# matrix_corin.net
KiCad netlist of a schematic drawn in Altium Designer
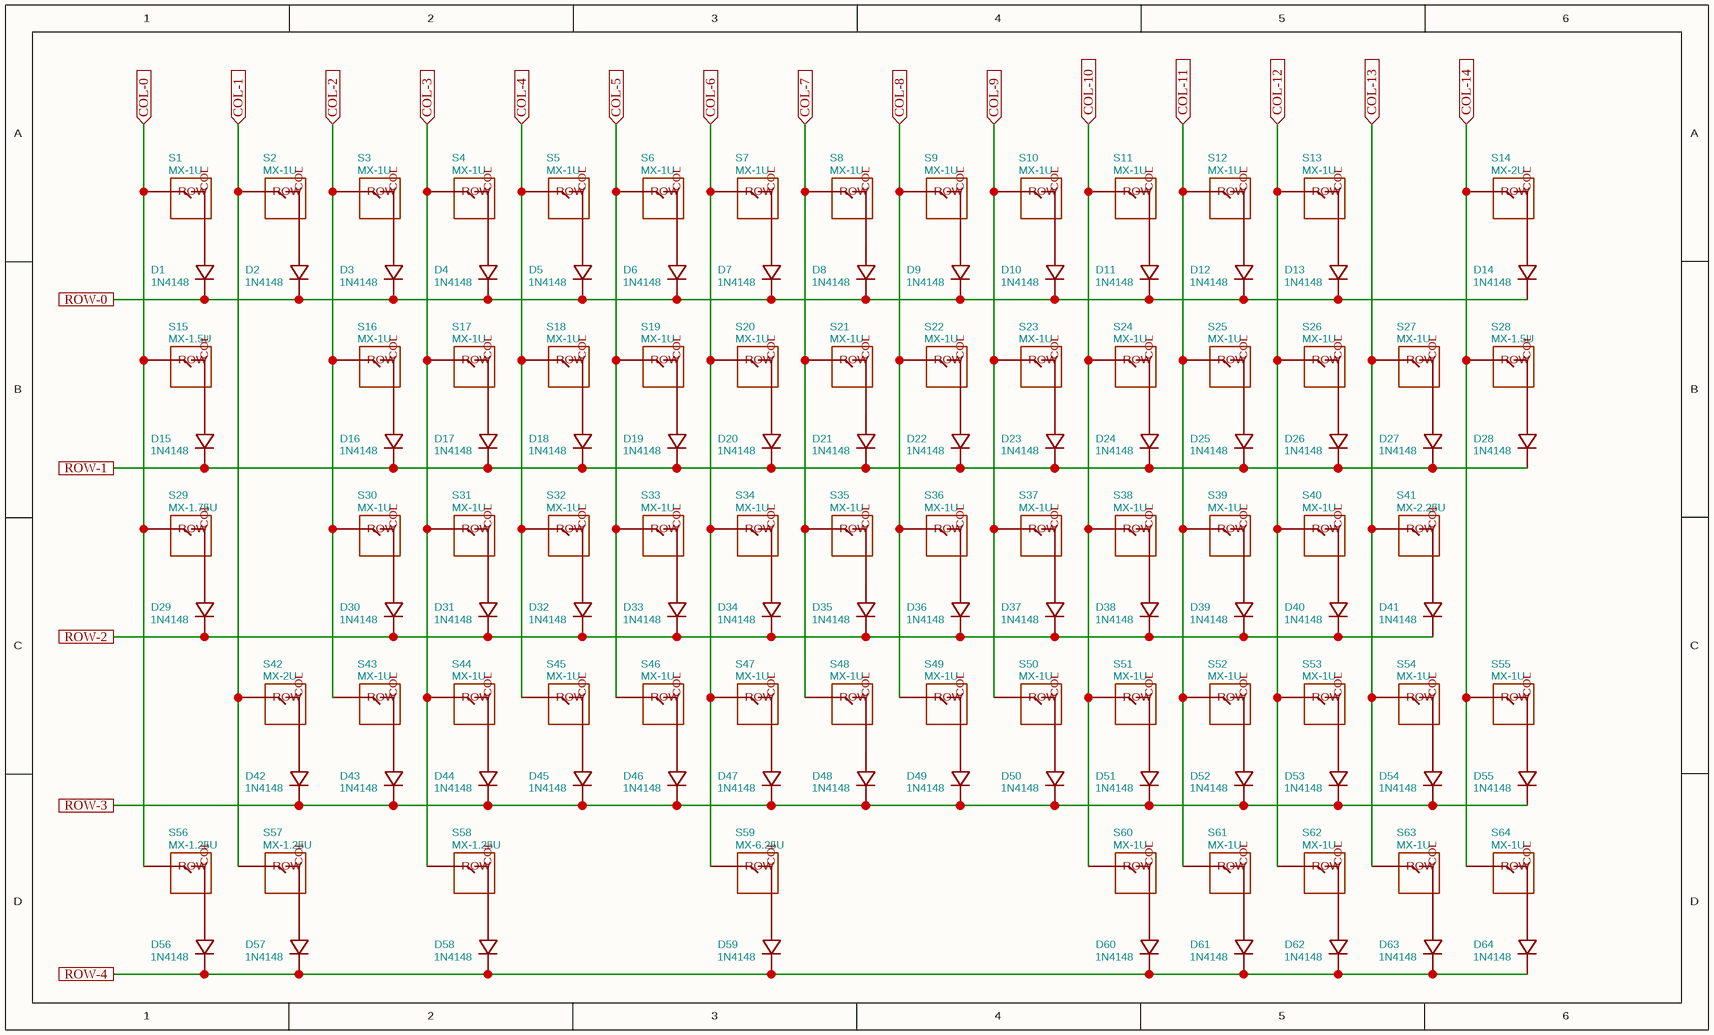
[diagram p0: matrix_corin.schdoc]

(export (version "E")
  (design (tool "Eeschema 10.0.6"))
  (components
    (comp (ref "D1")
      (value "1N4148")
      (fields (field (name "BOM_MANUFACTURER PART") "1N4148W") (field (name "BOM_SUPPLIER PART") "C115103"))
      (libsource (lib "altium-import") (part "root_1_1N4148_"))
    )
    (comp (ref "D2")
      (value "1N4148")
      (fields (field (name "BOM_MANUFACTURER PART") "1N4148W") (field (name "BOM_SUPPLIER PART") "C115103"))
      (libsource (lib "altium-import") (part "root_1_1N4148_"))
    )
    (comp (ref "D3")
      (value "1N4148")
      (fields (field (name "BOM_MANUFACTURER PART") "1N4148W") (field (name "BOM_SUPPLIER PART") "C115103"))
      (libsource (lib "altium-import") (part "root_1_1N4148_"))
    )
    (comp (ref "D4")
      (value "1N4148")
      (fields (field (name "BOM_MANUFACTURER PART") "1N4148W") (field (name "BOM_SUPPLIER PART") "C115103"))
      (libsource (lib "altium-import") (part "root_1_1N4148_"))
    )
    (comp (ref "D5")
      (value "1N4148")
      (fields (field (name "BOM_MANUFACTURER PART") "1N4148W") (field (name "BOM_SUPPLIER PART") "C115103"))
      (libsource (lib "altium-import") (part "root_1_1N4148_"))
    )
    (comp (ref "D6")
      (value "1N4148")
      (fields (field (name "BOM_MANUFACTURER PART") "1N4148W") (field (name "BOM_SUPPLIER PART") "C115103"))
      (libsource (lib "altium-import") (part "root_1_1N4148_"))
    )
    (comp (ref "D7")
      (value "1N4148")
      (fields (field (name "BOM_MANUFACTURER PART") "1N4148W") (field (name "BOM_SUPPLIER PART") "C115103"))
      (libsource (lib "altium-import") (part "root_1_1N4148_"))
    )
    (comp (ref "D8")
      (value "1N4148")
      (fields (field (name "BOM_MANUFACTURER PART") "1N4148W") (field (name "BOM_SUPPLIER PART") "C115103"))
      (libsource (lib "altium-import") (part "root_1_1N4148_"))
    )
    (comp (ref "D9")
      (value "1N4148")
      (fields (field (name "BOM_MANUFACTURER PART") "1N4148W") (field (name "BOM_SUPPLIER PART") "C115103"))
      (libsource (lib "altium-import") (part "root_1_1N4148_"))
    )
    (comp (ref "D10")
      (value "1N4148")
      (fields (field (name "BOM_MANUFACTURER PART") "1N4148W") (field (name "BOM_SUPPLIER PART") "C115103"))
      (libsource (lib "altium-import") (part "root_1_1N4148_"))
    )
    (comp (ref "D11")
      (value "1N4148")
      (fields (field (name "BOM_MANUFACTURER PART") "1N4148W") (field (name "BOM_SUPPLIER PART") "C115103"))
      (libsource (lib "altium-import") (part "root_1_1N4148_"))
    )
    (comp (ref "D12")
      (value "1N4148")
      (fields (field (name "BOM_MANUFACTURER PART") "1N4148W") (field (name "BOM_SUPPLIER PART") "C115103"))
      (libsource (lib "altium-import") (part "root_1_1N4148_"))
    )
    (comp (ref "D13")
      (value "1N4148")
      (fields (field (name "BOM_MANUFACTURER PART") "1N4148W") (field (name "BOM_SUPPLIER PART") "C115103"))
      (libsource (lib "altium-import") (part "root_1_1N4148_"))
    )
    (comp (ref "D14")
      (value "1N4148")
      (fields (field (name "BOM_MANUFACTURER PART") "1N4148W") (field (name "BOM_SUPPLIER PART") "C115103"))
      (libsource (lib "altium-import") (part "root_1_1N4148_"))
    )
    (comp (ref "D15")
      (value "1N4148")
      (fields (field (name "BOM_MANUFACTURER PART") "1N4148W") (field (name "BOM_SUPPLIER PART") "C115103"))
      (libsource (lib "altium-import") (part "root_1_1N4148_"))
    )
    (comp (ref "D16")
      (value "1N4148")
      (fields (field (name "BOM_MANUFACTURER PART") "1N4148W") (field (name "BOM_SUPPLIER PART") "C115103"))
      (libsource (lib "altium-import") (part "root_1_1N4148_"))
    )
    (comp (ref "D17")
      (value "1N4148")
      (fields (field (name "BOM_MANUFACTURER PART") "1N4148W") (field (name "BOM_SUPPLIER PART") "C115103"))
      (libsource (lib "altium-import") (part "root_1_1N4148_"))
    )
    (comp (ref "D18")
      (value "1N4148")
      (fields (field (name "BOM_MANUFACTURER PART") "1N4148W") (field (name "BOM_SUPPLIER PART") "C115103"))
      (libsource (lib "altium-import") (part "root_1_1N4148_"))
    )
    (comp (ref "D19")
      (value "1N4148")
      (fields (field (name "BOM_MANUFACTURER PART") "1N4148W") (field (name "BOM_SUPPLIER PART") "C115103"))
      (libsource (lib "altium-import") (part "root_1_1N4148_"))
    )
    (comp (ref "D20")
      (value "1N4148")
      (fields (field (name "BOM_MANUFACTURER PART") "1N4148W") (field (name "BOM_SUPPLIER PART") "C115103"))
      (libsource (lib "altium-import") (part "root_1_1N4148_"))
    )
    (comp (ref "D21")
      (value "1N4148")
      (fields (field (name "BOM_MANUFACTURER PART") "1N4148W") (field (name "BOM_SUPPLIER PART") "C115103"))
      (libsource (lib "altium-import") (part "root_1_1N4148_"))
    )
    (comp (ref "D22")
      (value "1N4148")
      (fields (field (name "BOM_MANUFACTURER PART") "1N4148W") (field (name "BOM_SUPPLIER PART") "C115103"))
      (libsource (lib "altium-import") (part "root_1_1N4148_"))
    )
    (comp (ref "D23")
      (value "1N4148")
      (fields (field (name "BOM_MANUFACTURER PART") "1N4148W") (field (name "BOM_SUPPLIER PART") "C115103"))
      (libsource (lib "altium-import") (part "root_1_1N4148_"))
    )
    (comp (ref "D24")
      (value "1N4148")
      (fields (field (name "BOM_MANUFACTURER PART") "1N4148W") (field (name "BOM_SUPPLIER PART") "C115103"))
      (libsource (lib "altium-import") (part "root_1_1N4148_"))
    )
    (comp (ref "D25")
      (value "1N4148")
      (fields (field (name "BOM_MANUFACTURER PART") "1N4148W") (field (name "BOM_SUPPLIER PART") "C115103"))
      (libsource (lib "altium-import") (part "root_1_1N4148_"))
    )
    (comp (ref "D26")
      (value "1N4148")
      (fields (field (name "BOM_MANUFACTURER PART") "1N4148W") (field (name "BOM_SUPPLIER PART") "C115103"))
      (libsource (lib "altium-import") (part "root_1_1N4148_"))
    )
    (comp (ref "D27")
      (value "1N4148")
      (fields (field (name "BOM_MANUFACTURER PART") "1N4148W") (field (name "BOM_SUPPLIER PART") "C115103"))
      (libsource (lib "altium-import") (part "root_1_1N4148_"))
    )
    (comp (ref "D28")
      (value "1N4148")
      (fields (field (name "BOM_MANUFACTURER PART") "1N4148W") (field (name "BOM_SUPPLIER PART") "C115103"))
      (libsource (lib "altium-import") (part "root_1_1N4148_"))
    )
    (comp (ref "D29")
      (value "1N4148")
      (fields (field (name "BOM_MANUFACTURER PART") "1N4148W") (field (name "BOM_SUPPLIER PART") "C115103"))
      (libsource (lib "altium-import") (part "root_1_1N4148_"))
    )
    (comp (ref "D30")
      (value "1N4148")
      (fields (field (name "BOM_MANUFACTURER PART") "1N4148W") (field (name "BOM_SUPPLIER PART") "C115103"))
      (libsource (lib "altium-import") (part "root_1_1N4148_"))
    )
    (comp (ref "D31")
      (value "1N4148")
      (fields (field (name "BOM_MANUFACTURER PART") "1N4148W") (field (name "BOM_SUPPLIER PART") "C115103"))
      (libsource (lib "altium-import") (part "root_1_1N4148_"))
    )
    (comp (ref "D32")
      (value "1N4148")
      (fields (field (name "BOM_MANUFACTURER PART") "1N4148W") (field (name "BOM_SUPPLIER PART") "C115103"))
      (libsource (lib "altium-import") (part "root_1_1N4148_"))
    )
    (comp (ref "D33")
      (value "1N4148")
      (fields (field (name "BOM_MANUFACTURER PART") "1N4148W") (field (name "BOM_SUPPLIER PART") "C115103"))
      (libsource (lib "altium-import") (part "root_1_1N4148_"))
    )
    (comp (ref "D34")
      (value "1N4148")
      (fields (field (name "BOM_MANUFACTURER PART") "1N4148W") (field (name "BOM_SUPPLIER PART") "C115103"))
      (libsource (lib "altium-import") (part "root_1_1N4148_"))
    )
    (comp (ref "D35")
      (value "1N4148")
      (fields (field (name "BOM_MANUFACTURER PART") "1N4148W") (field (name "BOM_SUPPLIER PART") "C115103"))
      (libsource (lib "altium-import") (part "root_1_1N4148_"))
    )
    (comp (ref "D36")
      (value "1N4148")
      (fields (field (name "BOM_MANUFACTURER PART") "1N4148W") (field (name "BOM_SUPPLIER PART") "C115103"))
      (libsource (lib "altium-import") (part "root_1_1N4148_"))
    )
    (comp (ref "D37")
      (value "1N4148")
      (fields (field (name "BOM_MANUFACTURER PART") "1N4148W") (field (name "BOM_SUPPLIER PART") "C115103"))
      (libsource (lib "altium-import") (part "root_1_1N4148_"))
    )
    (comp (ref "D38")
      (value "1N4148")
      (fields (field (name "BOM_MANUFACTURER PART") "1N4148W") (field (name "BOM_SUPPLIER PART") "C115103"))
      (libsource (lib "altium-import") (part "root_1_1N4148_"))
    )
    (comp (ref "D39")
      (value "1N4148")
      (fields (field (name "BOM_MANUFACTURER PART") "1N4148W") (field (name "BOM_SUPPLIER PART") "C115103"))
      (libsource (lib "altium-import") (part "root_1_1N4148_"))
    )
    (comp (ref "D40")
      (value "1N4148")
      (fields (field (name "BOM_MANUFACTURER PART") "1N4148W") (field (name "BOM_SUPPLIER PART") "C115103"))
      (libsource (lib "altium-import") (part "root_1_1N4148_"))
    )
    (comp (ref "D41")
      (value "1N4148")
      (fields (field (name "BOM_MANUFACTURER PART") "1N4148W") (field (name "BOM_SUPPLIER PART") "C115103"))
      (libsource (lib "altium-import") (part "root_1_1N4148_"))
    )
    (comp (ref "D42")
      (value "1N4148")
      (fields (field (name "BOM_MANUFACTURER PART") "1N4148W") (field (name "BOM_SUPPLIER PART") "C115103"))
      (libsource (lib "altium-import") (part "root_1_1N4148_"))
    )
    (comp (ref "D43")
      (value "1N4148")
      (fields (field (name "BOM_MANUFACTURER PART") "1N4148W") (field (name "BOM_SUPPLIER PART") "C115103"))
      (libsource (lib "altium-import") (part "root_1_1N4148_"))
    )
    (comp (ref "D44")
      (value "1N4148")
      (fields (field (name "BOM_MANUFACTURER PART") "1N4148W") (field (name "BOM_SUPPLIER PART") "C115103"))
      (libsource (lib "altium-import") (part "root_1_1N4148_"))
    )
    (comp (ref "D45")
      (value "1N4148")
      (fields (field (name "BOM_MANUFACTURER PART") "1N4148W") (field (name "BOM_SUPPLIER PART") "C115103"))
      (libsource (lib "altium-import") (part "root_1_1N4148_"))
    )
    (comp (ref "D46")
      (value "1N4148")
      (fields (field (name "BOM_MANUFACTURER PART") "1N4148W") (field (name "BOM_SUPPLIER PART") "C115103"))
      (libsource (lib "altium-import") (part "root_1_1N4148_"))
    )
    (comp (ref "D47")
      (value "1N4148")
      (fields (field (name "BOM_MANUFACTURER PART") "1N4148W") (field (name "BOM_SUPPLIER PART") "C115103"))
      (libsource (lib "altium-import") (part "root_1_1N4148_"))
    )
    (comp (ref "D48")
      (value "1N4148")
      (fields (field (name "BOM_MANUFACTURER PART") "1N4148W") (field (name "BOM_SUPPLIER PART") "C115103"))
      (libsource (lib "altium-import") (part "root_1_1N4148_"))
    )
    (comp (ref "D49")
      (value "1N4148")
      (fields (field (name "BOM_MANUFACTURER PART") "1N4148W") (field (name "BOM_SUPPLIER PART") "C115103"))
      (libsource (lib "altium-import") (part "root_1_1N4148_"))
    )
    (comp (ref "D50")
      (value "1N4148")
      (fields (field (name "BOM_MANUFACTURER PART") "1N4148W") (field (name "BOM_SUPPLIER PART") "C115103"))
      (libsource (lib "altium-import") (part "root_1_1N4148_"))
    )
    (comp (ref "D51")
      (value "1N4148")
      (fields (field (name "BOM_MANUFACTURER PART") "1N4148W") (field (name "BOM_SUPPLIER PART") "C115103"))
      (libsource (lib "altium-import") (part "root_1_1N4148_"))
    )
    (comp (ref "D52")
      (value "1N4148")
      (fields (field (name "BOM_MANUFACTURER PART") "1N4148W") (field (name "BOM_SUPPLIER PART") "C115103"))
      (libsource (lib "altium-import") (part "root_1_1N4148_"))
    )
    (comp (ref "D53")
      (value "1N4148")
      (fields (field (name "BOM_MANUFACTURER PART") "1N4148W") (field (name "BOM_SUPPLIER PART") "C115103"))
      (libsource (lib "altium-import") (part "root_1_1N4148_"))
    )
    (comp (ref "D54")
      (value "1N4148")
      (fields (field (name "BOM_MANUFACTURER PART") "1N4148W") (field (name "BOM_SUPPLIER PART") "C115103"))
      (libsource (lib "altium-import") (part "root_1_1N4148_"))
    )
    (comp (ref "D55")
      (value "1N4148")
      (fields (field (name "BOM_MANUFACTURER PART") "1N4148W") (field (name "BOM_SUPPLIER PART") "C115103"))
      (libsource (lib "altium-import") (part "root_1_1N4148_"))
    )
    (comp (ref "D56")
      (value "1N4148")
      (fields (field (name "BOM_MANUFACTURER PART") "1N4148W") (field (name "BOM_SUPPLIER PART") "C115103"))
      (libsource (lib "altium-import") (part "root_1_1N4148_"))
    )
    (comp (ref "D57")
      (value "1N4148")
      (fields (field (name "BOM_MANUFACTURER PART") "1N4148W") (field (name "BOM_SUPPLIER PART") "C115103"))
      (libsource (lib "altium-import") (part "root_1_1N4148_"))
    )
    (comp (ref "D58")
      (value "1N4148")
      (fields (field (name "BOM_MANUFACTURER PART") "1N4148W") (field (name "BOM_SUPPLIER PART") "C115103"))
      (libsource (lib "altium-import") (part "root_1_1N4148_"))
    )
    (comp (ref "D59")
      (value "1N4148")
      (fields (field (name "BOM_MANUFACTURER PART") "1N4148W") (field (name "BOM_SUPPLIER PART") "C115103"))
      (libsource (lib "altium-import") (part "root_1_1N4148_"))
    )
    (comp (ref "D60")
      (value "1N4148")
      (fields (field (name "BOM_MANUFACTURER PART") "1N4148W") (field (name "BOM_SUPPLIER PART") "C115103"))
      (libsource (lib "altium-import") (part "root_1_1N4148_"))
    )
    (comp (ref "D61")
      (value "1N4148")
      (fields (field (name "BOM_MANUFACTURER PART") "1N4148W") (field (name "BOM_SUPPLIER PART") "C115103"))
      (libsource (lib "altium-import") (part "root_1_1N4148_"))
    )
    (comp (ref "D62")
      (value "1N4148")
      (fields (field (name "BOM_MANUFACTURER PART") "1N4148W") (field (name "BOM_SUPPLIER PART") "C115103"))
      (libsource (lib "altium-import") (part "root_1_1N4148_"))
    )
    (comp (ref "D63")
      (value "1N4148")
      (fields (field (name "BOM_MANUFACTURER PART") "1N4148W") (field (name "BOM_SUPPLIER PART") "C115103"))
      (libsource (lib "altium-import") (part "root_1_1N4148_"))
    )
    (comp (ref "D64")
      (value "1N4148")
      (fields (field (name "BOM_MANUFACTURER PART") "1N4148W") (field (name "BOM_SUPPLIER PART") "C115103"))
      (libsource (lib "altium-import") (part "root_1_1N4148_"))
    )
    (comp (ref "S1")
      (value "MX-1U")
      (fields (field (name "BOM_MANUFACTURER PART") "Cherry MX") (field (name "CONTRIBUTOR") "Longnald"))
      (libsource (lib "altium-import") (part "root_0_MX-1U_"))
    )
    (comp (ref "S2")
      (value "MX-1U")
      (fields (field (name "BOM_MANUFACTURER PART") "Cherry MX") (field (name "CONTRIBUTOR") "Longnald"))
      (libsource (lib "altium-import") (part "root_0_MX-1U_"))
    )
    (comp (ref "S3")
      (value "MX-1U")
      (fields (field (name "BOM_MANUFACTURER PART") "Cherry MX") (field (name "CONTRIBUTOR") "Longnald"))
      (libsource (lib "altium-import") (part "root_0_MX-1U_"))
    )
    (comp (ref "S4")
      (value "MX-1U")
      (fields (field (name "BOM_MANUFACTURER PART") "Cherry MX") (field (name "CONTRIBUTOR") "Longnald"))
      (libsource (lib "altium-import") (part "root_0_MX-1U_"))
    )
    (comp (ref "S5")
      (value "MX-1U")
      (fields (field (name "BOM_MANUFACTURER PART") "Cherry MX") (field (name "CONTRIBUTOR") "Longnald"))
      (libsource (lib "altium-import") (part "root_0_MX-1U_"))
    )
    (comp (ref "S6")
      (value "MX-1U")
      (fields (field (name "BOM_MANUFACTURER PART") "Cherry MX") (field (name "CONTRIBUTOR") "Longnald"))
      (libsource (lib "altium-import") (part "root_0_MX-1U_"))
    )
    (comp (ref "S7")
      (value "MX-1U")
      (fields (field (name "BOM_MANUFACTURER PART") "Cherry MX") (field (name "CONTRIBUTOR") "Longnald"))
      (libsource (lib "altium-import") (part "root_0_MX-1U_"))
    )
    (comp (ref "S8")
      (value "MX-1U")
      (fields (field (name "BOM_MANUFACTURER PART") "Cherry MX") (field (name "CONTRIBUTOR") "Longnald"))
      (libsource (lib "altium-import") (part "root_0_MX-1U_"))
    )
    (comp (ref "S9")
      (value "MX-1U")
      (fields (field (name "BOM_MANUFACTURER PART") "Cherry MX") (field (name "CONTRIBUTOR") "Longnald"))
      (libsource (lib "altium-import") (part "root_0_MX-1U_"))
    )
    (comp (ref "S10")
      (value "MX-1U")
      (fields (field (name "BOM_MANUFACTURER PART") "Cherry MX") (field (name "CONTRIBUTOR") "Longnald"))
      (libsource (lib "altium-import") (part "root_0_MX-1U_"))
    )
    (comp (ref "S11")
      (value "MX-1U")
      (fields (field (name "BOM_MANUFACTURER PART") "Cherry MX") (field (name "CONTRIBUTOR") "Longnald"))
      (libsource (lib "altium-import") (part "root_0_MX-1U_"))
    )
    (comp (ref "S12")
      (value "MX-1U")
      (fields (field (name "BOM_MANUFACTURER PART") "Cherry MX") (field (name "CONTRIBUTOR") "Longnald"))
      (libsource (lib "altium-import") (part "root_0_MX-1U_"))
    )
    (comp (ref "S13")
      (value "MX-1U")
      (fields (field (name "BOM_MANUFACTURER PART") "Cherry MX") (field (name "CONTRIBUTOR") "Longnald"))
      (libsource (lib "altium-import") (part "root_0_MX-1U_"))
    )
    (comp (ref "S14")
      (value "MX-2U")
      (fields (field (name "BOM_MANUFACTURER PART") "CherryMX") (field (name "CONTRIBUTOR") "Longnald"))
      (libsource (lib "altium-import") (part "root_0_MX-2U_"))
    )
    (comp (ref "S15")
      (value "MX-1.5U")
      (fields (field (name "BOM_MANUFACTURER PART") "Cherry MX") (field (name "CONTRIBUTOR") "Longnald"))
      (libsource (lib "altium-import") (part "root_0_MX-1.5U_"))
    )
    (comp (ref "S16")
      (value "MX-1U")
      (fields (field (name "BOM_MANUFACTURER PART") "Cherry MX") (field (name "CONTRIBUTOR") "Longnald"))
      (libsource (lib "altium-import") (part "root_0_MX-1U_"))
    )
    (comp (ref "S17")
      (value "MX-1U")
      (fields (field (name "BOM_MANUFACTURER PART") "Cherry MX") (field (name "CONTRIBUTOR") "Longnald"))
      (libsource (lib "altium-import") (part "root_0_MX-1U_"))
    )
    (comp (ref "S18")
      (value "MX-1U")
      (fields (field (name "BOM_MANUFACTURER PART") "Cherry MX") (field (name "CONTRIBUTOR") "Longnald"))
      (libsource (lib "altium-import") (part "root_0_MX-1U_"))
    )
    (comp (ref "S19")
      (value "MX-1U")
      (fields (field (name "BOM_MANUFACTURER PART") "Cherry MX") (field (name "CONTRIBUTOR") "Longnald"))
      (libsource (lib "altium-import") (part "root_0_MX-1U_"))
    )
    (comp (ref "S20")
      (value "MX-1U")
      (fields (field (name "BOM_MANUFACTURER PART") "Cherry MX") (field (name "CONTRIBUTOR") "Longnald"))
      (libsource (lib "altium-import") (part "root_0_MX-1U_"))
    )
    (comp (ref "S21")
      (value "MX-1U")
      (fields (field (name "BOM_MANUFACTURER PART") "Cherry MX") (field (name "CONTRIBUTOR") "Longnald"))
      (libsource (lib "altium-import") (part "root_0_MX-1U_"))
    )
    (comp (ref "S22")
      (value "MX-1U")
      (fields (field (name "BOM_MANUFACTURER PART") "Cherry MX") (field (name "CONTRIBUTOR") "Longnald"))
      (libsource (lib "altium-import") (part "root_0_MX-1U_"))
    )
    (comp (ref "S23")
      (value "MX-1U")
      (fields (field (name "BOM_MANUFACTURER PART") "Cherry MX") (field (name "CONTRIBUTOR") "Longnald"))
      (libsource (lib "altium-import") (part "root_0_MX-1U_"))
    )
    (comp (ref "S24")
      (value "MX-1U")
      (fields (field (name "BOM_MANUFACTURER PART") "Cherry MX") (field (name "CONTRIBUTOR") "Longnald"))
      (libsource (lib "altium-import") (part "root_0_MX-1U_"))
    )
    (comp (ref "S25")
      (value "MX-1U")
      (fields (field (name "BOM_MANUFACTURER PART") "Cherry MX") (field (name "CONTRIBUTOR") "Longnald"))
      (libsource (lib "altium-import") (part "root_0_MX-1U_"))
    )
    (comp (ref "S26")
      (value "MX-1U")
      (fields (field (name "BOM_MANUFACTURER PART") "Cherry MX") (field (name "CONTRIBUTOR") "Longnald"))
      (libsource (lib "altium-import") (part "root_0_MX-1U_"))
    )
    (comp (ref "S27")
      (value "MX-1U")
      (fields (field (name "BOM_MANUFACTURER PART") "Cherry MX") (field (name "CONTRIBUTOR") "Longnald"))
      (libsource (lib "altium-import") (part "root_0_MX-1U_"))
    )
    (comp (ref "S28")
      (value "MX-1.5U")
      (fields (field (name "BOM_MANUFACTURER PART") "Cherry MX") (field (name "CONTRIBUTOR") "Longnald"))
      (libsource (lib "altium-import") (part "root_0_MX-1.5U_"))
    )
    (comp (ref "S29")
      (value "MX-1.75U")
      (fields (field (name "BOM_MANUFACTURER PART") "CherryMX") (field (name "CONTRIBUTOR") "Longnald"))
      (libsource (lib "altium-import") (part "root_0_MX-1.75U_"))
    )
    (comp (ref "S30")
      (value "MX-1U")
      (fields (field (name "BOM_MANUFACTURER PART") "Cherry MX") (field (name "CONTRIBUTOR") "Longnald"))
      (libsource (lib "altium-import") (part "root_0_MX-1U_"))
    )
    (comp (ref "S31")
      (value "MX-1U")
      (fields (field (name "BOM_MANUFACTURER PART") "Cherry MX") (field (name "CONTRIBUTOR") "Longnald"))
      (libsource (lib "altium-import") (part "root_0_MX-1U_"))
    )
    (comp (ref "S32")
      (value "MX-1U")
      (fields (field (name "BOM_MANUFACTURER PART") "Cherry MX") (field (name "CONTRIBUTOR") "Longnald"))
      (libsource (lib "altium-import") (part "root_0_MX-1U_"))
    )
    (comp (ref "S33")
      (value "MX-1U")
      (fields (field (name "BOM_MANUFACTURER PART") "Cherry MX") (field (name "CONTRIBUTOR") "Longnald"))
      (libsource (lib "altium-import") (part "root_0_MX-1U_"))
    )
    (comp (ref "S34")
      (value "MX-1U")
      (fields (field (name "BOM_MANUFACTURER PART") "Cherry MX") (field (name "CONTRIBUTOR") "Longnald"))
      (libsource (lib "altium-import") (part "root_0_MX-1U_"))
    )
    (comp (ref "S35")
      (value "MX-1U")
      (fields (field (name "BOM_MANUFACTURER PART") "Cherry MX") (field (name "CONTRIBUTOR") "Longnald"))
      (libsource (lib "altium-import") (part "root_0_MX-1U_"))
    )
    (comp (ref "S36")
      (value "MX-1U")
      (fields (field (name "BOM_MANUFACTURER PART") "Cherry MX") (field (name "CONTRIBUTOR") "Longnald"))
      (libsource (lib "altium-import") (part "root_0_MX-1U_"))
    )
    (comp (ref "S37")
      (value "MX-1U")
      (fields (field (name "BOM_MANUFACTURER PART") "Cherry MX") (field (name "CONTRIBUTOR") "Longnald"))
      (libsource (lib "altium-import") (part "root_0_MX-1U_"))
    )
    (comp (ref "S38")
      (value "MX-1U")
      (fields (field (name "BOM_MANUFACTURER PART") "Cherry MX") (field (name "CONTRIBUTOR") "Longnald"))
      (libsource (lib "altium-import") (part "root_0_MX-1U_"))
    )
    (comp (ref "S39")
      (value "MX-1U")
      (fields (field (name "BOM_MANUFACTURER PART") "Cherry MX") (field (name "CONTRIBUTOR") "Longnald"))
      (libsource (lib "altium-import") (part "root_0_MX-1U_"))
    )
    (comp (ref "S40")
      (value "MX-1U")
      (fields (field (name "BOM_MANUFACTURER PART") "Cherry MX") (field (name "CONTRIBUTOR") "Longnald"))
      (libsource (lib "altium-import") (part "root_0_MX-1U_"))
    )
    (comp (ref "S41")
      (value "MX-2.25U")
      (fields (field (name "BOM_MANUFACTURER PART") "CherryMX") (field (name "CONTRIBUTOR") "Longnald"))
      (libsource (lib "altium-import") (part "root_0_MX-2.25U_"))
    )
    (comp (ref "S42")
      (value "MX-2U")
      (fields (field (name "BOM_MANUFACTURER PART") "CherryMX") (field (name "CONTRIBUTOR") "Longnald"))
      (libsource (lib "altium-import") (part "root_0_MX-2U_"))
    )
    (comp (ref "S43")
      (value "MX-1U")
      (fields (field (name "BOM_MANUFACTURER PART") "Cherry MX") (field (name "CONTRIBUTOR") "Longnald"))
      (libsource (lib "altium-import") (part "root_0_MX-1U_"))
    )
    (comp (ref "S44")
      (value "MX-1U")
      (fields (field (name "BOM_MANUFACTURER PART") "Cherry MX") (field (name "CONTRIBUTOR") "Longnald"))
      (libsource (lib "altium-import") (part "root_0_MX-1U_"))
    )
    (comp (ref "S45")
      (value "MX-1U")
      (fields (field (name "BOM_MANUFACTURER PART") "Cherry MX") (field (name "CONTRIBUTOR") "Longnald"))
      (libsource (lib "altium-import") (part "root_0_MX-1U_"))
    )
    (comp (ref "S46")
      (value "MX-1U")
      (fields (field (name "BOM_MANUFACTURER PART") "Cherry MX") (field (name "CONTRIBUTOR") "Longnald"))
      (libsource (lib "altium-import") (part "root_0_MX-1U_"))
    )
    (comp (ref "S47")
      (value "MX-1U")
      (fields (field (name "BOM_MANUFACTURER PART") "Cherry MX") (field (name "CONTRIBUTOR") "Longnald"))
      (libsource (lib "altium-import") (part "root_0_MX-1U_"))
    )
    (comp (ref "S48")
      (value "MX-1U")
      (fields (field (name "BOM_MANUFACTURER PART") "Cherry MX") (field (name "CONTRIBUTOR") "Longnald"))
      (libsource (lib "altium-import") (part "root_0_MX-1U_"))
    )
    (comp (ref "S49")
      (value "MX-1U")
      (fields (field (name "BOM_MANUFACTURER PART") "Cherry MX") (field (name "CONTRIBUTOR") "Longnald"))
      (libsource (lib "altium-import") (part "root_0_MX-1U_"))
    )
    (comp (ref "S50")
      (value "MX-1U")
      (fields (field (name "BOM_MANUFACTURER PART") "Cherry MX") (field (name "CONTRIBUTOR") "Longnald"))
      (libsource (lib "altium-import") (part "root_0_MX-1U_"))
    )
    (comp (ref "S51")
      (value "MX-1U")
      (fields (field (name "BOM_MANUFACTURER PART") "Cherry MX") (field (name "CONTRIBUTOR") "Longnald"))
      (libsource (lib "altium-import") (part "root_0_MX-1U_"))
    )
    (comp (ref "S52")
      (value "MX-1U")
      (fields (field (name "BOM_MANUFACTURER PART") "Cherry MX") (field (name "CONTRIBUTOR") "Longnald"))
      (libsource (lib "altium-import") (part "root_0_MX-1U_"))
    )
    (comp (ref "S53")
      (value "MX-1U")
      (fields (field (name "BOM_MANUFACTURER PART") "Cherry MX") (field (name "CONTRIBUTOR") "Longnald"))
      (libsource (lib "altium-import") (part "root_0_MX-1U_"))
    )
    (comp (ref "S54")
      (value "MX-1U")
      (fields (field (name "BOM_MANUFACTURER PART") "Cherry MX") (field (name "CONTRIBUTOR") "Longnald"))
      (libsource (lib "altium-import") (part "root_0_MX-1U_"))
    )
    (comp (ref "S55")
      (value "MX-1U")
      (fields (field (name "BOM_MANUFACTURER PART") "Cherry MX") (field (name "CONTRIBUTOR") "Longnald"))
      (libsource (lib "altium-import") (part "root_0_MX-1U_"))
    )
    (comp (ref "S56")
      (value "MX-1.25U")
      (fields (field (name "BOM_MANUFACTURER PART") "CherryMX") (field (name "CONTRIBUTOR") "Longnald"))
      (libsource (lib "altium-import") (part "root_0_MX-1.25U_"))
    )
    (comp (ref "S57")
      (value "MX-1.25U")
      (fields (field (name "BOM_MANUFACTURER PART") "CherryMX") (field (name "CONTRIBUTOR") "Longnald"))
      (libsource (lib "altium-import") (part "root_0_MX-1.25U_"))
    )
    (comp (ref "S58")
      (value "MX-1.25U")
      (fields (field (name "BOM_MANUFACTURER PART") "CherryMX") (field (name "CONTRIBUTOR") "Longnald"))
      (libsource (lib "altium-import") (part "root_0_MX-1.25U_"))
    )
    (comp (ref "S59")
      (value "MX-6.25U")
      (fields (field (name "BOM_MANUFACTURER PART") "CherryMX") (field (name "CONTRIBUTOR") "Longnald"))
      (libsource (lib "altium-import") (part "root_0_MX-6.25U_"))
    )
    (comp (ref "S60")
      (value "MX-1U")
      (fields (field (name "BOM_MANUFACTURER PART") "Cherry MX") (field (name "CONTRIBUTOR") "Longnald"))
      (libsource (lib "altium-import") (part "root_0_MX-1U_"))
    )
    (comp (ref "S61")
      (value "MX-1U")
      (fields (field (name "BOM_MANUFACTURER PART") "Cherry MX") (field (name "CONTRIBUTOR") "Longnald"))
      (libsource (lib "altium-import") (part "root_0_MX-1U_"))
    )
    (comp (ref "S62")
      (value "MX-1U")
      (fields (field (name "BOM_MANUFACTURER PART") "Cherry MX") (field (name "CONTRIBUTOR") "Longnald"))
      (libsource (lib "altium-import") (part "root_0_MX-1U_"))
    )
    (comp (ref "S63")
      (value "MX-1U")
      (fields (field (name "BOM_MANUFACTURER PART") "Cherry MX") (field (name "CONTRIBUTOR") "Longnald"))
      (libsource (lib "altium-import") (part "root_0_MX-1U_"))
    )
    (comp (ref "S64")
      (value "MX-1U")
      (fields (field (name "BOM_MANUFACTURER PART") "Cherry MX") (field (name "CONTRIBUTOR") "Longnald"))
      (libsource (lib "altium-import") (part "root_0_MX-1U_"))
    )
  )
  (nets
    (net (code "1") (name "/COL-0") (class "Default")
      (node (ref "S1") (pin "ROW") (pinfunction "ROW_ROW") (pintype "passive"))
      (node (ref "S15") (pin "ROW") (pinfunction "ROW_ROW") (pintype "passive"))
      (node (ref "S29") (pin "ROW") (pinfunction "ROW_ROW") (pintype "passive"))
      (node (ref "S56") (pin "ROW") (pinfunction "ROW_ROW") (pintype "passive"))
    )
    (net (code "2") (name "/COL-1") (class "Default")
      (node (ref "S2") (pin "ROW") (pinfunction "ROW_ROW") (pintype "passive"))
      (node (ref "S42") (pin "ROW") (pinfunction "ROW_ROW") (pintype "passive"))
      (node (ref "S57") (pin "ROW") (pinfunction "ROW_ROW") (pintype "passive"))
    )
    (net (code "3") (name "/COL-2") (class "Default")
      (node (ref "S16") (pin "ROW") (pinfunction "ROW_ROW") (pintype "passive"))
      (node (ref "S3") (pin "ROW") (pinfunction "ROW_ROW") (pintype "passive"))
      (node (ref "S30") (pin "ROW") (pinfunction "ROW_ROW") (pintype "passive"))
      (node (ref "S43") (pin "ROW") (pinfunction "ROW_ROW") (pintype "passive"))
    )
    (net (code "4") (name "/COL-3") (class "Default")
      (node (ref "S17") (pin "ROW") (pinfunction "ROW_ROW") (pintype "passive"))
      (node (ref "S31") (pin "ROW") (pinfunction "ROW_ROW") (pintype "passive"))
      (node (ref "S4") (pin "ROW") (pinfunction "ROW_ROW") (pintype "passive"))
      (node (ref "S44") (pin "ROW") (pinfunction "ROW_ROW") (pintype "passive"))
      (node (ref "S58") (pin "ROW") (pinfunction "ROW_ROW") (pintype "passive"))
    )
    (net (code "5") (name "/COL-4") (class "Default")
      (node (ref "S18") (pin "ROW") (pinfunction "ROW_ROW") (pintype "passive"))
      (node (ref "S32") (pin "ROW") (pinfunction "ROW_ROW") (pintype "passive"))
      (node (ref "S45") (pin "ROW") (pinfunction "ROW_ROW") (pintype "passive"))
      (node (ref "S5") (pin "ROW") (pinfunction "ROW_ROW") (pintype "passive"))
    )
    (net (code "6") (name "/COL-5") (class "Default")
      (node (ref "S19") (pin "ROW") (pinfunction "ROW_ROW") (pintype "passive"))
      (node (ref "S33") (pin "ROW") (pinfunction "ROW_ROW") (pintype "passive"))
      (node (ref "S46") (pin "ROW") (pinfunction "ROW_ROW") (pintype "passive"))
      (node (ref "S6") (pin "ROW") (pinfunction "ROW_ROW") (pintype "passive"))
    )
    (net (code "7") (name "/COL-6") (class "Default")
      (node (ref "S20") (pin "ROW") (pinfunction "ROW_ROW") (pintype "passive"))
      (node (ref "S34") (pin "ROW") (pinfunction "ROW_ROW") (pintype "passive"))
      (node (ref "S47") (pin "ROW") (pinfunction "ROW_ROW") (pintype "passive"))
      (node (ref "S59") (pin "ROW") (pinfunction "ROW_ROW") (pintype "passive"))
      (node (ref "S7") (pin "ROW") (pinfunction "ROW_ROW") (pintype "passive"))
    )
    (net (code "8") (name "/COL-7") (class "Default")
      (node (ref "S21") (pin "ROW") (pinfunction "ROW_ROW") (pintype "passive"))
      (node (ref "S35") (pin "ROW") (pinfunction "ROW_ROW") (pintype "passive"))
      (node (ref "S48") (pin "ROW") (pinfunction "ROW_ROW") (pintype "passive"))
      (node (ref "S8") (pin "ROW") (pinfunction "ROW_ROW") (pintype "passive"))
    )
    (net (code "9") (name "/COL-8") (class "Default")
      (node (ref "S22") (pin "ROW") (pinfunction "ROW_ROW") (pintype "passive"))
      (node (ref "S36") (pin "ROW") (pinfunction "ROW_ROW") (pintype "passive"))
      (node (ref "S49") (pin "ROW") (pinfunction "ROW_ROW") (pintype "passive"))
      (node (ref "S9") (pin "ROW") (pinfunction "ROW_ROW") (pintype "passive"))
    )
    (net (code "10") (name "/COL-9") (class "Default")
      (node (ref "S10") (pin "ROW") (pinfunction "ROW_ROW") (pintype "passive"))
      (node (ref "S23") (pin "ROW") (pinfunction "ROW_ROW") (pintype "passive"))
      (node (ref "S37") (pin "ROW") (pinfunction "ROW_ROW") (pintype "passive"))
      (node (ref "S50") (pin "ROW") (pinfunction "ROW_ROW") (pintype "passive"))
    )
    (net (code "11") (name "/COL-10") (class "Default")
      (node (ref "S11") (pin "ROW") (pinfunction "ROW_ROW") (pintype "passive"))
      (node (ref "S24") (pin "ROW") (pinfunction "ROW_ROW") (pintype "passive"))
      (node (ref "S38") (pin "ROW") (pinfunction "ROW_ROW") (pintype "passive"))
      (node (ref "S51") (pin "ROW") (pinfunction "ROW_ROW") (pintype "passive"))
      (node (ref "S60") (pin "ROW") (pinfunction "ROW_ROW") (pintype "passive"))
    )
    (net (code "12") (name "/COL-11") (class "Default")
      (node (ref "S12") (pin "ROW") (pinfunction "ROW_ROW") (pintype "passive"))
      (node (ref "S25") (pin "ROW") (pinfunction "ROW_ROW") (pintype "passive"))
      (node (ref "S39") (pin "ROW") (pinfunction "ROW_ROW") (pintype "passive"))
      (node (ref "S52") (pin "ROW") (pinfunction "ROW_ROW") (pintype "passive"))
      (node (ref "S61") (pin "ROW") (pinfunction "ROW_ROW") (pintype "passive"))
    )
    (net (code "13") (name "/COL-12") (class "Default")
      (node (ref "S13") (pin "ROW") (pinfunction "ROW_ROW") (pintype "passive"))
      (node (ref "S26") (pin "ROW") (pinfunction "ROW_ROW") (pintype "passive"))
      (node (ref "S40") (pin "ROW") (pinfunction "ROW_ROW") (pintype "passive"))
      (node (ref "S53") (pin "ROW") (pinfunction "ROW_ROW") (pintype "passive"))
      (node (ref "S62") (pin "ROW") (pinfunction "ROW_ROW") (pintype "passive"))
    )
    (net (code "14") (name "/COL-13") (class "Default")
      (node (ref "S27") (pin "ROW") (pinfunction "ROW_ROW") (pintype "passive"))
      (node (ref "S41") (pin "ROW") (pinfunction "ROW_ROW") (pintype "passive"))
      (node (ref "S54") (pin "ROW") (pinfunction "ROW_ROW") (pintype "passive"))
      (node (ref "S63") (pin "ROW") (pinfunction "ROW_ROW") (pintype "passive"))
    )
    (net (code "15") (name "/COL-14") (class "Default")
      (node (ref "S14") (pin "ROW") (pinfunction "ROW_ROW") (pintype "passive"))
      (node (ref "S28") (pin "ROW") (pinfunction "ROW_ROW") (pintype "passive"))
      (node (ref "S55") (pin "ROW") (pinfunction "ROW_ROW") (pintype "passive"))
      (node (ref "S64") (pin "ROW") (pinfunction "ROW_ROW") (pintype "passive"))
    )
    (net (code "21") (name "Net-(D1-A)") (class "Default")
      (node (ref "D1") (pin "2") (pinfunction "A_2") (pintype "passive"))
      (node (ref "S1") (pin "COL") (pinfunction "COL_COL") (pintype "passive"))
    )
    (net (code "22") (name "Net-(D1-K)") (class "Default")
      (node (ref "D1") (pin "1") (pinfunction "K_1") (pintype "passive"))
      (node (ref "D10") (pin "1") (pinfunction "K_1") (pintype "passive"))
      (node (ref "D11") (pin "1") (pinfunction "K_1") (pintype "passive"))
      (node (ref "D12") (pin "1") (pinfunction "K_1") (pintype "passive"))
      (node (ref "D13") (pin "1") (pinfunction "K_1") (pintype "passive"))
      (node (ref "D14") (pin "1") (pinfunction "K_1") (pintype "passive"))
      (node (ref "D2") (pin "1") (pinfunction "K_1") (pintype "passive"))
      (node (ref "D3") (pin "1") (pinfunction "K_1") (pintype "passive"))
      (node (ref "D4") (pin "1") (pinfunction "K_1") (pintype "passive"))
      (node (ref "D5") (pin "1") (pinfunction "K_1") (pintype "passive"))
      (node (ref "D6") (pin "1") (pinfunction "K_1") (pintype "passive"))
      (node (ref "D7") (pin "1") (pinfunction "K_1") (pintype "passive"))
      (node (ref "D8") (pin "1") (pinfunction "K_1") (pintype "passive"))
      (node (ref "D9") (pin "1") (pinfunction "K_1") (pintype "passive"))
    )
    (net (code "23") (name "Net-(D2-A)") (class "Default")
      (node (ref "D2") (pin "2") (pinfunction "A_2") (pintype "passive"))
      (node (ref "S2") (pin "COL") (pinfunction "COL_COL") (pintype "passive"))
    )
    (net (code "24") (name "Net-(D3-A)") (class "Default")
      (node (ref "D3") (pin "2") (pinfunction "A_2") (pintype "passive"))
      (node (ref "S3") (pin "COL") (pinfunction "COL_COL") (pintype "passive"))
    )
    (net (code "25") (name "Net-(D4-A)") (class "Default")
      (node (ref "D4") (pin "2") (pinfunction "A_2") (pintype "passive"))
      (node (ref "S4") (pin "COL") (pinfunction "COL_COL") (pintype "passive"))
    )
    (net (code "26") (name "Net-(D5-A)") (class "Default")
      (node (ref "D5") (pin "2") (pinfunction "A_2") (pintype "passive"))
      (node (ref "S5") (pin "COL") (pinfunction "COL_COL") (pintype "passive"))
    )
    (net (code "27") (name "Net-(D6-A)") (class "Default")
      (node (ref "D6") (pin "2") (pinfunction "A_2") (pintype "passive"))
      (node (ref "S6") (pin "COL") (pinfunction "COL_COL") (pintype "passive"))
    )
    (net (code "28") (name "Net-(D7-A)") (class "Default")
      (node (ref "D7") (pin "2") (pinfunction "A_2") (pintype "passive"))
      (node (ref "S7") (pin "COL") (pinfunction "COL_COL") (pintype "passive"))
    )
    (net (code "29") (name "Net-(D8-A)") (class "Default")
      (node (ref "D8") (pin "2") (pinfunction "A_2") (pintype "passive"))
      (node (ref "S8") (pin "COL") (pinfunction "COL_COL") (pintype "passive"))
    )
    (net (code "30") (name "Net-(D9-A)") (class "Default")
      (node (ref "D9") (pin "2") (pinfunction "A_2") (pintype "passive"))
      (node (ref "S9") (pin "COL") (pinfunction "COL_COL") (pintype "passive"))
    )
    (net (code "31") (name "Net-(D10-A)") (class "Default")
      (node (ref "D10") (pin "2") (pinfunction "A_2") (pintype "passive"))
      (node (ref "S10") (pin "COL") (pinfunction "COL_COL") (pintype "passive"))
    )
    (net (code "32") (name "Net-(D11-A)") (class "Default")
      (node (ref "D11") (pin "2") (pinfunction "A_2") (pintype "passive"))
      (node (ref "S11") (pin "COL") (pinfunction "COL_COL") (pintype "passive"))
    )
    (net (code "33") (name "Net-(D12-A)") (class "Default")
      (node (ref "D12") (pin "2") (pinfunction "A_2") (pintype "passive"))
      (node (ref "S12") (pin "COL") (pinfunction "COL_COL") (pintype "passive"))
    )
    (net (code "34") (name "Net-(D13-A)") (class "Default")
      (node (ref "D13") (pin "2") (pinfunction "A_2") (pintype "passive"))
      (node (ref "S13") (pin "COL") (pinfunction "COL_COL") (pintype "passive"))
    )
    (net (code "35") (name "Net-(D14-A)") (class "Default")
      (node (ref "D14") (pin "2") (pinfunction "A_2") (pintype "passive"))
      (node (ref "S14") (pin "COL") (pinfunction "COL_COL") (pintype "passive"))
    )
    (net (code "36") (name "Net-(D15-A)") (class "Default")
      (node (ref "D15") (pin "2") (pinfunction "A_2") (pintype "passive"))
      (node (ref "S15") (pin "COL") (pinfunction "COL_COL") (pintype "passive"))
    )
    (net (code "37") (name "Net-(D15-K)") (class "Default")
      (node (ref "D15") (pin "1") (pinfunction "K_1") (pintype "passive"))
      (node (ref "D16") (pin "1") (pinfunction "K_1") (pintype "passive"))
      (node (ref "D17") (pin "1") (pinfunction "K_1") (pintype "passive"))
      (node (ref "D18") (pin "1") (pinfunction "K_1") (pintype "passive"))
      (node (ref "D19") (pin "1") (pinfunction "K_1") (pintype "passive"))
      (node (ref "D20") (pin "1") (pinfunction "K_1") (pintype "passive"))
      (node (ref "D21") (pin "1") (pinfunction "K_1") (pintype "passive"))
      (node (ref "D22") (pin "1") (pinfunction "K_1") (pintype "passive"))
      (node (ref "D23") (pin "1") (pinfunction "K_1") (pintype "passive"))
      (node (ref "D24") (pin "1") (pinfunction "K_1") (pintype "passive"))
      (node (ref "D25") (pin "1") (pinfunction "K_1") (pintype "passive"))
      (node (ref "D26") (pin "1") (pinfunction "K_1") (pintype "passive"))
      (node (ref "D27") (pin "1") (pinfunction "K_1") (pintype "passive"))
      (node (ref "D28") (pin "1") (pinfunction "K_1") (pintype "passive"))
    )
    (net (code "38") (name "Net-(D16-A)") (class "Default")
      (node (ref "D16") (pin "2") (pinfunction "A_2") (pintype "passive"))
      (node (ref "S16") (pin "COL") (pinfunction "COL_COL") (pintype "passive"))
    )
    (net (code "39") (name "Net-(D17-A)") (class "Default")
      (node (ref "D17") (pin "2") (pinfunction "A_2") (pintype "passive"))
      (node (ref "S17") (pin "COL") (pinfunction "COL_COL") (pintype "passive"))
    )
    (net (code "40") (name "Net-(D18-A)") (class "Default")
      (node (ref "D18") (pin "2") (pinfunction "A_2") (pintype "passive"))
      (node (ref "S18") (pin "COL") (pinfunction "COL_COL") (pintype "passive"))
    )
    (net (code "41") (name "Net-(D19-A)") (class "Default")
      (node (ref "D19") (pin "2") (pinfunction "A_2") (pintype "passive"))
      (node (ref "S19") (pin "COL") (pinfunction "COL_COL") (pintype "passive"))
    )
    (net (code "42") (name "Net-(D20-A)") (class "Default")
      (node (ref "D20") (pin "2") (pinfunction "A_2") (pintype "passive"))
      (node (ref "S20") (pin "COL") (pinfunction "COL_COL") (pintype "passive"))
    )
    (net (code "43") (name "Net-(D21-A)") (class "Default")
      (node (ref "D21") (pin "2") (pinfunction "A_2") (pintype "passive"))
      (node (ref "S21") (pin "COL") (pinfunction "COL_COL") (pintype "passive"))
    )
    (net (code "44") (name "Net-(D22-A)") (class "Default")
      (node (ref "D22") (pin "2") (pinfunction "A_2") (pintype "passive"))
      (node (ref "S22") (pin "COL") (pinfunction "COL_COL") (pintype "passive"))
    )
    (net (code "45") (name "Net-(D23-A)") (class "Default")
      (node (ref "D23") (pin "2") (pinfunction "A_2") (pintype "passive"))
      (node (ref "S23") (pin "COL") (pinfunction "COL_COL") (pintype "passive"))
    )
    (net (code "46") (name "Net-(D24-A)") (class "Default")
      (node (ref "D24") (pin "2") (pinfunction "A_2") (pintype "passive"))
      (node (ref "S24") (pin "COL") (pinfunction "COL_COL") (pintype "passive"))
    )
    (net (code "47") (name "Net-(D25-A)") (class "Default")
      (node (ref "D25") (pin "2") (pinfunction "A_2") (pintype "passive"))
      (node (ref "S25") (pin "COL") (pinfunction "COL_COL") (pintype "passive"))
    )
    (net (code "48") (name "Net-(D26-A)") (class "Default")
      (node (ref "D26") (pin "2") (pinfunction "A_2") (pintype "passive"))
      (node (ref "S26") (pin "COL") (pinfunction "COL_COL") (pintype "passive"))
    )
    (net (code "49") (name "Net-(D27-A)") (class "Default")
      (node (ref "D27") (pin "2") (pinfunction "A_2") (pintype "passive"))
      (node (ref "S27") (pin "COL") (pinfunction "COL_COL") (pintype "passive"))
    )
    (net (code "50") (name "Net-(D28-A)") (class "Default")
      (node (ref "D28") (pin "2") (pinfunction "A_2") (pintype "passive"))
      (node (ref "S28") (pin "COL") (pinfunction "COL_COL") (pintype "passive"))
    )
    (net (code "51") (name "Net-(D29-A)") (class "Default")
      (node (ref "D29") (pin "2") (pinfunction "A_2") (pintype "passive"))
      (node (ref "S29") (pin "COL") (pinfunction "COL_COL") (pintype "passive"))
    )
    (net (code "52") (name "Net-(D29-K)") (class "Default")
      (node (ref "D29") (pin "1") (pinfunction "K_1") (pintype "passive"))
      (node (ref "D30") (pin "1") (pinfunction "K_1") (pintype "passive"))
      (node (ref "D31") (pin "1") (pinfunction "K_1") (pintype "passive"))
      (node (ref "D32") (pin "1") (pinfunction "K_1") (pintype "passive"))
      (node (ref "D33") (pin "1") (pinfunction "K_1") (pintype "passive"))
      (node (ref "D34") (pin "1") (pinfunction "K_1") (pintype "passive"))
      (node (ref "D35") (pin "1") (pinfunction "K_1") (pintype "passive"))
      (node (ref "D36") (pin "1") (pinfunction "K_1") (pintype "passive"))
      (node (ref "D37") (pin "1") (pinfunction "K_1") (pintype "passive"))
      (node (ref "D38") (pin "1") (pinfunction "K_1") (pintype "passive"))
      (node (ref "D39") (pin "1") (pinfunction "K_1") (pintype "passive"))
      (node (ref "D40") (pin "1") (pinfunction "K_1") (pintype "passive"))
      (node (ref "D41") (pin "1") (pinfunction "K_1") (pintype "passive"))
    )
    (net (code "53") (name "Net-(D30-A)") (class "Default")
      (node (ref "D30") (pin "2") (pinfunction "A_2") (pintype "passive"))
      (node (ref "S30") (pin "COL") (pinfunction "COL_COL") (pintype "passive"))
    )
    (net (code "54") (name "Net-(D31-A)") (class "Default")
      (node (ref "D31") (pin "2") (pinfunction "A_2") (pintype "passive"))
      (node (ref "S31") (pin "COL") (pinfunction "COL_COL") (pintype "passive"))
    )
    (net (code "55") (name "Net-(D32-A)") (class "Default")
      (node (ref "D32") (pin "2") (pinfunction "A_2") (pintype "passive"))
      (node (ref "S32") (pin "COL") (pinfunction "COL_COL") (pintype "passive"))
    )
    (net (code "56") (name "Net-(D33-A)") (class "Default")
      (node (ref "D33") (pin "2") (pinfunction "A_2") (pintype "passive"))
      (node (ref "S33") (pin "COL") (pinfunction "COL_COL") (pintype "passive"))
    )
    (net (code "57") (name "Net-(D34-A)") (class "Default")
      (node (ref "D34") (pin "2") (pinfunction "A_2") (pintype "passive"))
      (node (ref "S34") (pin "COL") (pinfunction "COL_COL") (pintype "passive"))
    )
    (net (code "58") (name "Net-(D35-A)") (class "Default")
      (node (ref "D35") (pin "2") (pinfunction "A_2") (pintype "passive"))
      (node (ref "S35") (pin "COL") (pinfunction "COL_COL") (pintype "passive"))
    )
    (net (code "59") (name "Net-(D36-A)") (class "Default")
      (node (ref "D36") (pin "2") (pinfunction "A_2") (pintype "passive"))
      (node (ref "S36") (pin "COL") (pinfunction "COL_COL") (pintype "passive"))
    )
    (net (code "60") (name "Net-(D37-A)") (class "Default")
      (node (ref "D37") (pin "2") (pinfunction "A_2") (pintype "passive"))
      (node (ref "S37") (pin "COL") (pinfunction "COL_COL") (pintype "passive"))
    )
    (net (code "61") (name "Net-(D38-A)") (class "Default")
      (node (ref "D38") (pin "2") (pinfunction "A_2") (pintype "passive"))
      (node (ref "S38") (pin "COL") (pinfunction "COL_COL") (pintype "passive"))
    )
    (net (code "62") (name "Net-(D39-A)") (class "Default")
      (node (ref "D39") (pin "2") (pinfunction "A_2") (pintype "passive"))
      (node (ref "S39") (pin "COL") (pinfunction "COL_COL") (pintype "passive"))
    )
    (net (code "63") (name "Net-(D40-A)") (class "Default")
      (node (ref "D40") (pin "2") (pinfunction "A_2") (pintype "passive"))
      (node (ref "S40") (pin "COL") (pinfunction "COL_COL") (pintype "passive"))
    )
    (net (code "64") (name "Net-(D41-A)") (class "Default")
      (node (ref "D41") (pin "2") (pinfunction "A_2") (pintype "passive"))
      (node (ref "S41") (pin "COL") (pinfunction "COL_COL") (pintype "passive"))
    )
    (net (code "65") (name "Net-(D42-A)") (class "Default")
      (node (ref "D42") (pin "2") (pinfunction "A_2") (pintype "passive"))
      (node (ref "S42") (pin "COL") (pinfunction "COL_COL") (pintype "passive"))
    )
    (net (code "66") (name "Net-(D42-K)") (class "Default")
      (node (ref "D42") (pin "1") (pinfunction "K_1") (pintype "passive"))
      (node (ref "D43") (pin "1") (pinfunction "K_1") (pintype "passive"))
      (node (ref "D44") (pin "1") (pinfunction "K_1") (pintype "passive"))
      (node (ref "D45") (pin "1") (pinfunction "K_1") (pintype "passive"))
      (node (ref "D46") (pin "1") (pinfunction "K_1") (pintype "passive"))
      (node (ref "D47") (pin "1") (pinfunction "K_1") (pintype "passive"))
      (node (ref "D48") (pin "1") (pinfunction "K_1") (pintype "passive"))
      (node (ref "D49") (pin "1") (pinfunction "K_1") (pintype "passive"))
      (node (ref "D50") (pin "1") (pinfunction "K_1") (pintype "passive"))
      (node (ref "D51") (pin "1") (pinfunction "K_1") (pintype "passive"))
      (node (ref "D52") (pin "1") (pinfunction "K_1") (pintype "passive"))
      (node (ref "D53") (pin "1") (pinfunction "K_1") (pintype "passive"))
      (node (ref "D54") (pin "1") (pinfunction "K_1") (pintype "passive"))
      (node (ref "D55") (pin "1") (pinfunction "K_1") (pintype "passive"))
    )
    (net (code "67") (name "Net-(D43-A)") (class "Default")
      (node (ref "D43") (pin "2") (pinfunction "A_2") (pintype "passive"))
      (node (ref "S43") (pin "COL") (pinfunction "COL_COL") (pintype "passive"))
    )
    (net (code "68") (name "Net-(D44-A)") (class "Default")
      (node (ref "D44") (pin "2") (pinfunction "A_2") (pintype "passive"))
      (node (ref "S44") (pin "COL") (pinfunction "COL_COL") (pintype "passive"))
    )
    (net (code "69") (name "Net-(D45-A)") (class "Default")
      (node (ref "D45") (pin "2") (pinfunction "A_2") (pintype "passive"))
      (node (ref "S45") (pin "COL") (pinfunction "COL_COL") (pintype "passive"))
    )
    (net (code "70") (name "Net-(D46-A)") (class "Default")
      (node (ref "D46") (pin "2") (pinfunction "A_2") (pintype "passive"))
      (node (ref "S46") (pin "COL") (pinfunction "COL_COL") (pintype "passive"))
    )
    (net (code "71") (name "Net-(D47-A)") (class "Default")
      (node (ref "D47") (pin "2") (pinfunction "A_2") (pintype "passive"))
      (node (ref "S47") (pin "COL") (pinfunction "COL_COL") (pintype "passive"))
    )
    (net (code "72") (name "Net-(D48-A)") (class "Default")
      (node (ref "D48") (pin "2") (pinfunction "A_2") (pintype "passive"))
      (node (ref "S48") (pin "COL") (pinfunction "COL_COL") (pintype "passive"))
    )
    (net (code "73") (name "Net-(D49-A)") (class "Default")
      (node (ref "D49") (pin "2") (pinfunction "A_2") (pintype "passive"))
      (node (ref "S49") (pin "COL") (pinfunction "COL_COL") (pintype "passive"))
    )
    (net (code "74") (name "Net-(D50-A)") (class "Default")
      (node (ref "D50") (pin "2") (pinfunction "A_2") (pintype "passive"))
      (node (ref "S50") (pin "COL") (pinfunction "COL_COL") (pintype "passive"))
    )
    (net (code "75") (name "Net-(D51-A)") (class "Default")
      (node (ref "D51") (pin "2") (pinfunction "A_2") (pintype "passive"))
      (node (ref "S51") (pin "COL") (pinfunction "COL_COL") (pintype "passive"))
    )
    (net (code "76") (name "Net-(D52-A)") (class "Default")
      (node (ref "D52") (pin "2") (pinfunction "A_2") (pintype "passive"))
      (node (ref "S52") (pin "COL") (pinfunction "COL_COL") (pintype "passive"))
    )
    (net (code "77") (name "Net-(D53-A)") (class "Default")
      (node (ref "D53") (pin "2") (pinfunction "A_2") (pintype "passive"))
      (node (ref "S53") (pin "COL") (pinfunction "COL_COL") (pintype "passive"))
    )
    (net (code "78") (name "Net-(D54-A)") (class "Default")
      (node (ref "D54") (pin "2") (pinfunction "A_2") (pintype "passive"))
      (node (ref "S54") (pin "COL") (pinfunction "COL_COL") (pintype "passive"))
    )
    (net (code "79") (name "Net-(D55-A)") (class "Default")
      (node (ref "D55") (pin "2") (pinfunction "A_2") (pintype "passive"))
      (node (ref "S55") (pin "COL") (pinfunction "COL_COL") (pintype "passive"))
    )
    (net (code "80") (name "Net-(D56-A)") (class "Default")
      (node (ref "D56") (pin "2") (pinfunction "A_2") (pintype "passive"))
      (node (ref "S56") (pin "COL") (pinfunction "COL_COL") (pintype "passive"))
    )
    (net (code "81") (name "Net-(D56-K)") (class "Default")
      (node (ref "D56") (pin "1") (pinfunction "K_1") (pintype "passive"))
      (node (ref "D57") (pin "1") (pinfunction "K_1") (pintype "passive"))
      (node (ref "D58") (pin "1") (pinfunction "K_1") (pintype "passive"))
      (node (ref "D59") (pin "1") (pinfunction "K_1") (pintype "passive"))
      (node (ref "D60") (pin "1") (pinfunction "K_1") (pintype "passive"))
      (node (ref "D61") (pin "1") (pinfunction "K_1") (pintype "passive"))
      (node (ref "D62") (pin "1") (pinfunction "K_1") (pintype "passive"))
      (node (ref "D63") (pin "1") (pinfunction "K_1") (pintype "passive"))
      (node (ref "D64") (pin "1") (pinfunction "K_1") (pintype "passive"))
    )
    (net (code "82") (name "Net-(D57-A)") (class "Default")
      (node (ref "D57") (pin "2") (pinfunction "A_2") (pintype "passive"))
      (node (ref "S57") (pin "COL") (pinfunction "COL_COL") (pintype "passive"))
    )
    (net (code "83") (name "Net-(D58-A)") (class "Default")
      (node (ref "D58") (pin "2") (pinfunction "A_2") (pintype "passive"))
      (node (ref "S58") (pin "COL") (pinfunction "COL_COL") (pintype "passive"))
    )
    (net (code "84") (name "Net-(D59-A)") (class "Default")
      (node (ref "D59") (pin "2") (pinfunction "A_2") (pintype "passive"))
      (node (ref "S59") (pin "COL") (pinfunction "COL_COL") (pintype "passive"))
    )
    (net (code "85") (name "Net-(D60-A)") (class "Default")
      (node (ref "D60") (pin "2") (pinfunction "A_2") (pintype "passive"))
      (node (ref "S60") (pin "COL") (pinfunction "COL_COL") (pintype "passive"))
    )
    (net (code "86") (name "Net-(D61-A)") (class "Default")
      (node (ref "D61") (pin "2") (pinfunction "A_2") (pintype "passive"))
      (node (ref "S61") (pin "COL") (pinfunction "COL_COL") (pintype "passive"))
    )
    (net (code "87") (name "Net-(D62-A)") (class "Default")
      (node (ref "D62") (pin "2") (pinfunction "A_2") (pintype "passive"))
      (node (ref "S62") (pin "COL") (pinfunction "COL_COL") (pintype "passive"))
    )
    (net (code "88") (name "Net-(D63-A)") (class "Default")
      (node (ref "D63") (pin "2") (pinfunction "A_2") (pintype "passive"))
      (node (ref "S63") (pin "COL") (pinfunction "COL_COL") (pintype "passive"))
    )
    (net (code "89") (name "Net-(D64-A)") (class "Default")
      (node (ref "D64") (pin "2") (pinfunction "A_2") (pintype "passive"))
      (node (ref "S64") (pin "COL") (pinfunction "COL_COL") (pintype "passive"))
    )
  )
)
